# Gateway.net
KiCad netlist of a schematic drawn in EasyEDA Pro
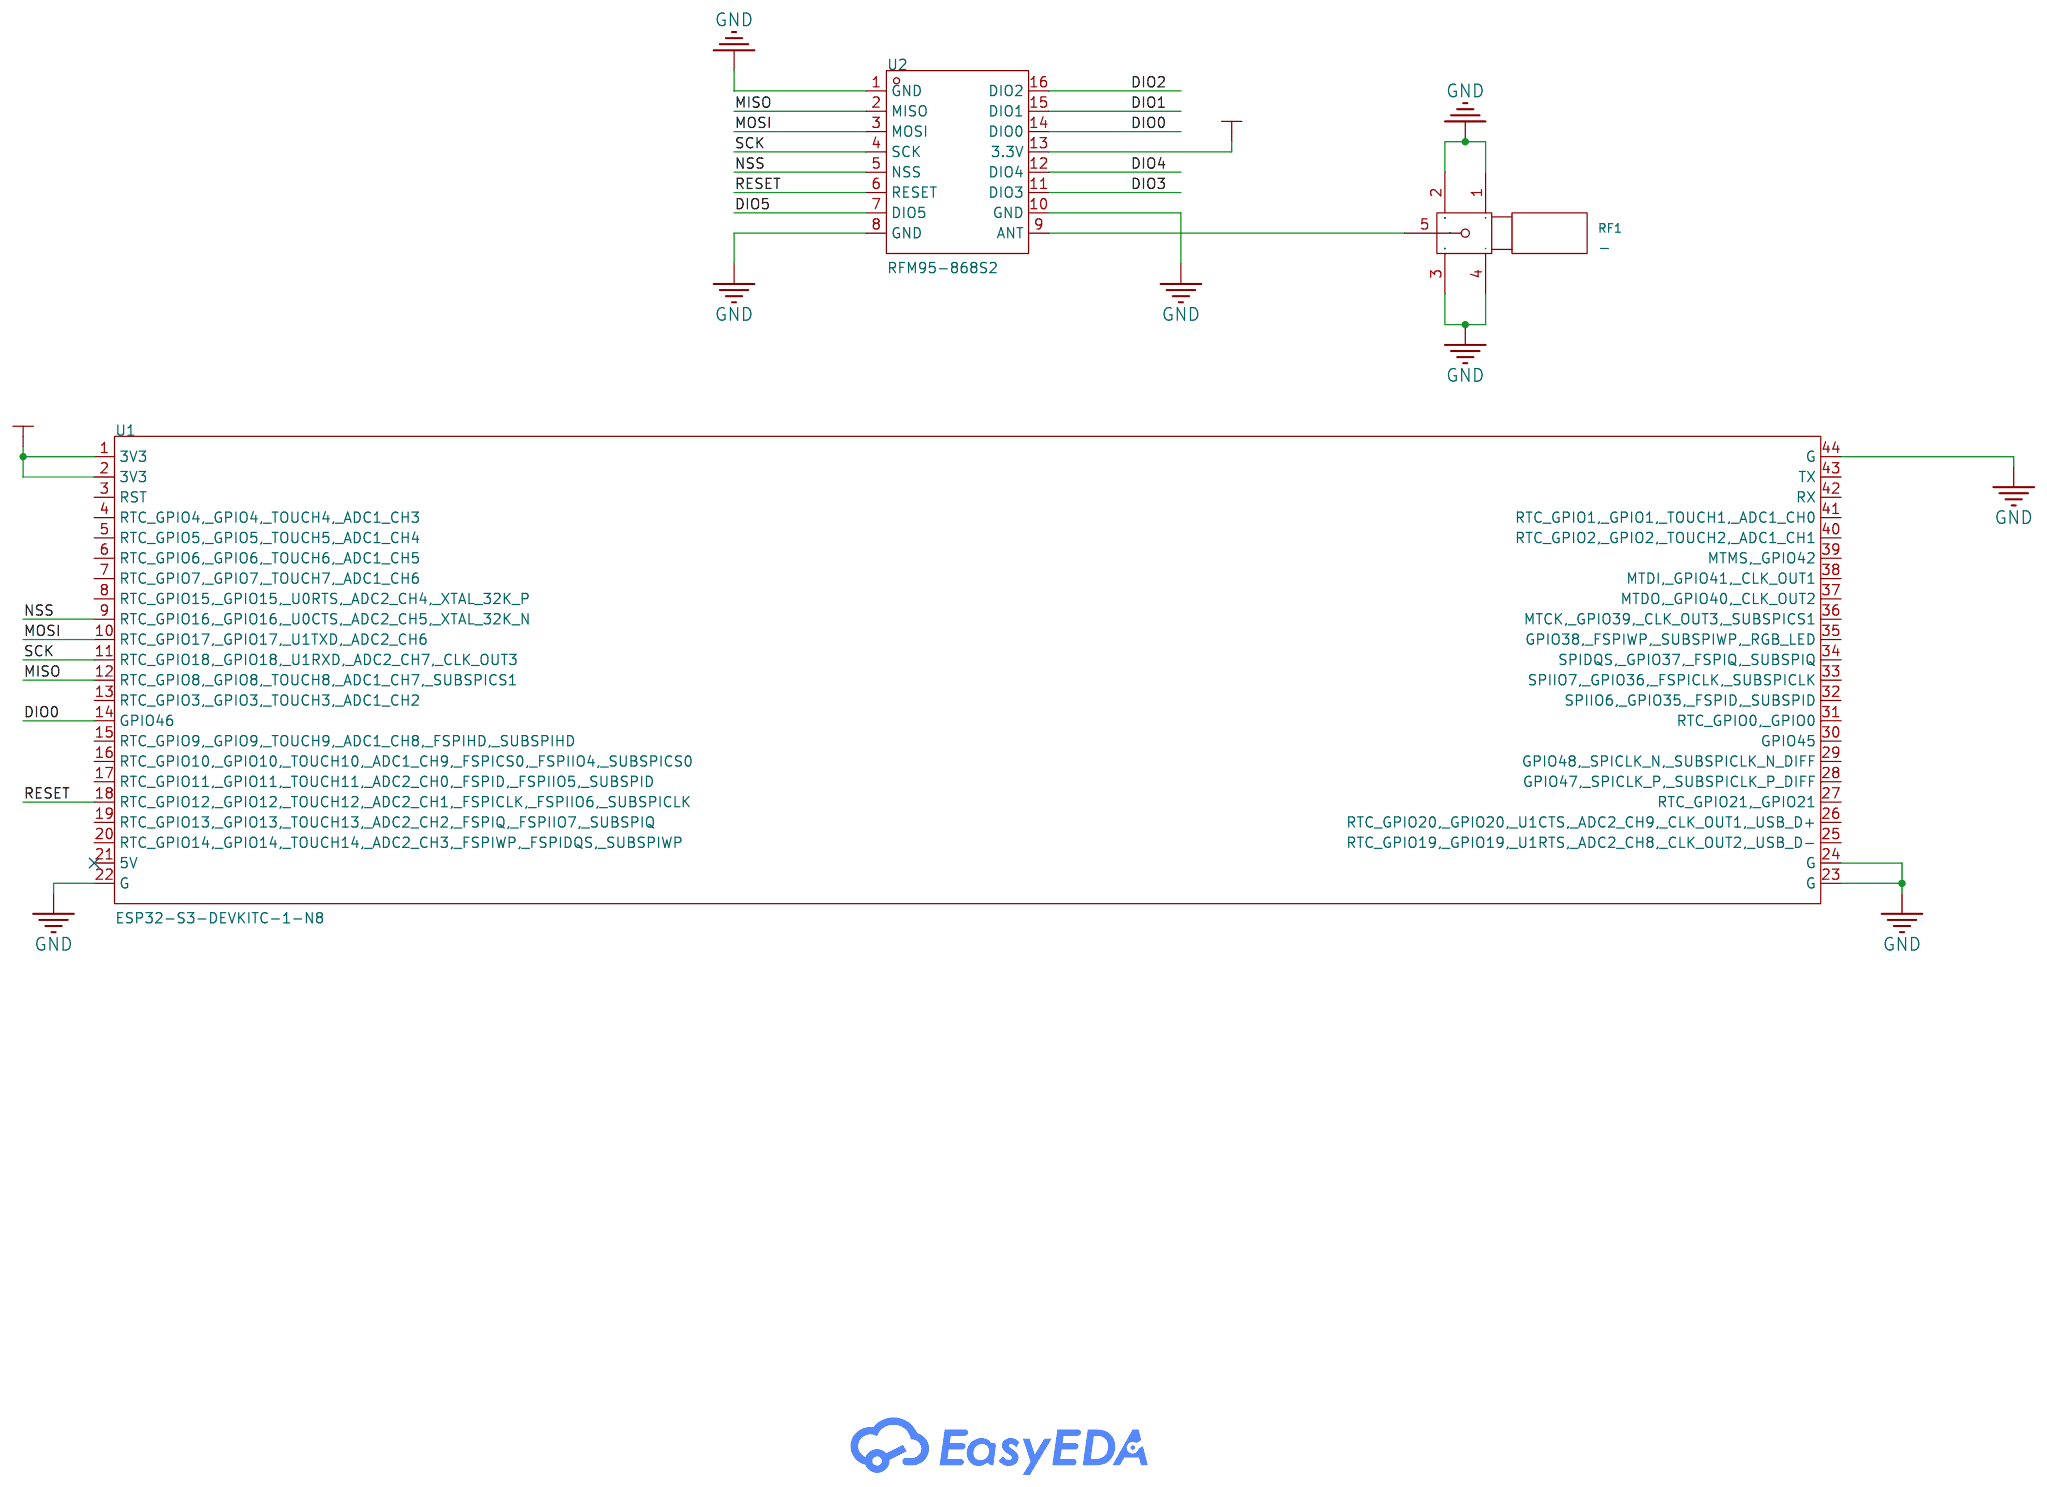
[diagram p0: schematic sheet]

(export (version "E")
  (design (tool "Eeschema 10.0.6"))
  (components
    (comp (ref "RF1")
      (value "-")
      (footprint "easyedapro:SMA-TH_BWSMA-KWE-Z001")
      (fields
        (field (name "Manufacturer Part") "BWSMA-KWE-Z001")
        (field (name "Manufacturer") "BAT WIRELESS(蝙蝠无线)")
      )
      (libsource (lib "easyedapro") (part "BWSMA-KWE-Z001"))
    )
    (comp (ref "U1")
      (value "ESP32-S3-DEVKITC-1-N8")
      (footprint "easyedapro:CONN-TH_ESP32-S3-DEVKITC-1U-N8")
      (fields (field (name "Manufacturer") "ESPRESSIF(乐鑫)"))
      (libsource (lib "easyedapro") (part "ESP32-S3-DEVKITC-1-N8"))
    )
    (comp (ref "U2")
      (value "RFM95-868S2")
      (footprint "easyedapro:WIRELM-SMD_RFM95-868S2")
      (fields (field (name "Manufacturer") "HOPERF(华普微电子)"))
      (libsource (lib "easyedapro") (part "RFM95-868S2"))
    )
  )
  (nets
    (net (code "1") (name "+3V3") (class "Default")
      (node (ref "U1") (pin "1") (pinfunction "3V3_1") (pintype "unspecified"))
      (node (ref "U1") (pin "2") (pinfunction "3V3_2") (pintype "unspecified"))
      (node (ref "U2") (pin "13") (pinfunction "3.3V_13") (pintype "unspecified"))
    )
    (net (code "2") (name "/DIO0") (class "Default")
      (node (ref "U1") (pin "14") (pinfunction "GPIO46_14") (pintype "unspecified"))
      (node (ref "U2") (pin "14") (pinfunction "DIO0_14") (pintype "unspecified"))
    )
    (net (code "3") (name "/DIO1") (class "Default")
      (node (ref "U2") (pin "15") (pinfunction "DIO1_15") (pintype "unspecified"))
    )
    (net (code "4") (name "/DIO2") (class "Default")
      (node (ref "U2") (pin "16") (pinfunction "DIO2_16") (pintype "unspecified"))
    )
    (net (code "5") (name "/DIO3") (class "Default")
      (node (ref "U2") (pin "11") (pinfunction "DIO3_11") (pintype "unspecified"))
    )
    (net (code "6") (name "/DIO4") (class "Default")
      (node (ref "U2") (pin "12") (pinfunction "DIO4_12") (pintype "unspecified"))
    )
    (net (code "7") (name "/DIO5") (class "Default")
      (node (ref "U2") (pin "7") (pinfunction "DIO5_7") (pintype "unspecified"))
    )
    (net (code "8") (name "/MISO") (class "Default")
      (node (ref "U1") (pin "12") (pinfunction "RTC_GPIO8,_GPIO8,_TOUCH8,_ADC1_CH7,_SUBSPICS1_12") (pintype "unspecified"))
      (node (ref "U2") (pin "2") (pinfunction "MISO_2") (pintype "unspecified"))
    )
    (net (code "9") (name "/MOSI") (class "Default")
      (node (ref "U1") (pin "10") (pinfunction "RTC_GPIO17,_GPIO17,_U1TXD,_ADC2_CH6_10") (pintype "unspecified"))
      (node (ref "U2") (pin "3") (pinfunction "MOSI_3") (pintype "unspecified"))
    )
    (net (code "10") (name "/NSS") (class "Default")
      (node (ref "U1") (pin "9") (pinfunction "RTC_GPIO16,_GPIO16,_U0CTS,_ADC2_CH5,_XTAL_32K_N_9") (pintype "unspecified"))
      (node (ref "U2") (pin "5") (pinfunction "NSS_5") (pintype "unspecified"))
    )
    (net (code "11") (name "/RESET") (class "Default")
      (node (ref "U1") (pin "18") (pinfunction "RTC_GPIO12,_GPIO12,_TOUCH12,_ADC2_CH1,_FSPICLK,_FSPIIO6,_SUBSPICLK_18") (pintype "unspecified"))
      (node (ref "U2") (pin "6") (pinfunction "RESET_6") (pintype "unspecified"))
    )
    (net (code "12") (name "/SCK") (class "Default")
      (node (ref "U1") (pin "11") (pinfunction "RTC_GPIO18,_GPIO18,_U1RXD,_ADC2_CH7,_CLK_OUT3_11") (pintype "unspecified"))
      (node (ref "U2") (pin "4") (pinfunction "SCK_4") (pintype "unspecified"))
    )
    (net (code "13") (name "GND") (class "Default")
      (node (ref "RF1") (pin "1") (pinfunction "1_1") (pintype "input"))
      (node (ref "RF1") (pin "2") (pinfunction "2_2") (pintype "input"))
      (node (ref "RF1") (pin "3") (pinfunction "3_3") (pintype "input"))
      (node (ref "RF1") (pin "4") (pinfunction "4_4") (pintype "input"))
      (node (ref "U1") (pin "22") (pinfunction "G_22") (pintype "unspecified"))
      (node (ref "U1") (pin "23") (pinfunction "G_23") (pintype "unspecified"))
      (node (ref "U1") (pin "24") (pinfunction "G_24") (pintype "unspecified"))
      (node (ref "U1") (pin "44") (pinfunction "G_44") (pintype "unspecified"))
      (node (ref "U2") (pin "1") (pinfunction "GND_1") (pintype "unspecified"))
      (node (ref "U2") (pin "10") (pinfunction "GND_10") (pintype "unspecified"))
      (node (ref "U2") (pin "8") (pinfunction "GND_8") (pintype "unspecified"))
    )
    (net (code "14") (name "Net-(U2-ANT)") (class "Default")
      (node (ref "RF1") (pin "5") (pinfunction "5_5") (pintype "input"))
      (node (ref "U2") (pin "9") (pinfunction "ANT_9") (pintype "unspecified"))
    )
    (net (code "15") (name "unconnected-(U1-5V-Pad21)") (class "Default")
      (node (ref "U1") (pin "21") (pinfunction "5V_21") (pintype "unspecified+no_connect"))
    )
    (net (code "16") (name "unconnected-(U1-GPIO38,_FSPIWP,_SUBSPIWP,_RGB_LED-Pad35)") (class "Default")
      (node (ref "U1") (pin "35") (pinfunction "GPIO38,_FSPIWP,_SUBSPIWP,_RGB_LED_35") (pintype "unspecified"))
    )
    (net (code "17") (name "unconnected-(U1-GPIO45-Pad30)") (class "Default")
      (node (ref "U1") (pin "30") (pinfunction "GPIO45_30") (pintype "unspecified"))
    )
    (net (code "18") (name "unconnected-(U1-GPIO47,_SPICLK_P,_SUBSPICLK_P_DIFF-Pad28)") (class "Default")
      (node (ref "U1") (pin "28") (pinfunction "GPIO47,_SPICLK_P,_SUBSPICLK_P_DIFF_28") (pintype "unspecified"))
    )
    (net (code "19") (name "unconnected-(U1-GPIO48,_SPICLK_N,_SUBSPICLK_N_DIFF-Pad29)") (class "Default")
      (node (ref "U1") (pin "29") (pinfunction "GPIO48,_SPICLK_N,_SUBSPICLK_N_DIFF_29") (pintype "unspecified"))
    )
    (net (code "20") (name "unconnected-(U1-MTCK,_GPIO39,_CLK_OUT3,_SUBSPICS1-Pad36)") (class "Default")
      (node (ref "U1") (pin "36") (pinfunction "MTCK,_GPIO39,_CLK_OUT3,_SUBSPICS1_36") (pintype "unspecified"))
    )
    (net (code "21") (name "unconnected-(U1-MTDI,_GPIO41,_CLK_OUT1-Pad38)") (class "Default")
      (node (ref "U1") (pin "38") (pinfunction "MTDI,_GPIO41,_CLK_OUT1_38") (pintype "unspecified"))
    )
    (net (code "22") (name "unconnected-(U1-MTDO,_GPIO40,_CLK_OUT2-Pad37)") (class "Default")
      (node (ref "U1") (pin "37") (pinfunction "MTDO,_GPIO40,_CLK_OUT2_37") (pintype "unspecified"))
    )
    (net (code "23") (name "unconnected-(U1-MTMS,_GPIO42-Pad39)") (class "Default")
      (node (ref "U1") (pin "39") (pinfunction "MTMS,_GPIO42_39") (pintype "unspecified"))
    )
    (net (code "24") (name "unconnected-(U1-RST-Pad3)") (class "Default")
      (node (ref "U1") (pin "3") (pinfunction "RST_3") (pintype "unspecified"))
    )
    (net (code "25") (name "unconnected-(U1-RTC_GPIO0,_GPIO0-Pad31)") (class "Default")
      (node (ref "U1") (pin "31") (pinfunction "RTC_GPIO0,_GPIO0_31") (pintype "unspecified"))
    )
    (net (code "26") (name "unconnected-(U1-RTC_GPIO1,_GPIO1,_TOUCH1,_ADC1_CH0-Pad41)") (class "Default")
      (node (ref "U1") (pin "41") (pinfunction "RTC_GPIO1,_GPIO1,_TOUCH1,_ADC1_CH0_41") (pintype "unspecified"))
    )
    (net (code "27") (name "unconnected-(U1-RTC_GPIO2,_GPIO2,_TOUCH2,_ADC1_CH1-Pad40)") (class "Default")
      (node (ref "U1") (pin "40") (pinfunction "RTC_GPIO2,_GPIO2,_TOUCH2,_ADC1_CH1_40") (pintype "unspecified"))
    )
    (net (code "28") (name "unconnected-(U1-RTC_GPIO3,_GPIO3,_TOUCH3,_ADC1_CH2-Pad13)") (class "Default")
      (node (ref "U1") (pin "13") (pinfunction "RTC_GPIO3,_GPIO3,_TOUCH3,_ADC1_CH2_13") (pintype "unspecified"))
    )
    (net (code "29") (name "unconnected-(U1-RTC_GPIO4,_GPIO4,_TOUCH4,_ADC1_CH3-Pad4)") (class "Default")
      (node (ref "U1") (pin "4") (pinfunction "RTC_GPIO4,_GPIO4,_TOUCH4,_ADC1_CH3_4") (pintype "unspecified"))
    )
    (net (code "30") (name "unconnected-(U1-RTC_GPIO5,_GPIO5,_TOUCH5,_ADC1_CH4-Pad5)") (class "Default")
      (node (ref "U1") (pin "5") (pinfunction "RTC_GPIO5,_GPIO5,_TOUCH5,_ADC1_CH4_5") (pintype "unspecified"))
    )
    (net (code "31") (name "unconnected-(U1-RTC_GPIO6,_GPIO6,_TOUCH6,_ADC1_CH5-Pad6)") (class "Default")
      (node (ref "U1") (pin "6") (pinfunction "RTC_GPIO6,_GPIO6,_TOUCH6,_ADC1_CH5_6") (pintype "unspecified"))
    )
    (net (code "32") (name "unconnected-(U1-RTC_GPIO7,_GPIO7,_TOUCH7,_ADC1_CH6-Pad7)") (class "Default")
      (node (ref "U1") (pin "7") (pinfunction "RTC_GPIO7,_GPIO7,_TOUCH7,_ADC1_CH6_7") (pintype "unspecified"))
    )
    (net (code "33") (name "unconnected-(U1-RTC_GPIO9,_GPIO9,_TOUCH9,_ADC1_CH8,_FSPIHD,_SUBSPIHD-Pad15)") (class "Default")
      (node (ref "U1") (pin "15") (pinfunction "RTC_GPIO9,_GPIO9,_TOUCH9,_ADC1_CH8,_FSPIHD,_SUBSPIHD_15") (pintype "unspecified"))
    )
    (net (code "34") (name "unconnected-(U1-RTC_GPIO10,_GPIO10,_TOUCH10,_ADC1_CH9,_FSPICS0,_FSPIIO4,_SUBSPICS0-Pad16)") (class "Default")
      (node (ref "U1") (pin "16") (pinfunction "RTC_GPIO10,_GPIO10,_TOUCH10,_ADC1_CH9,_FSPICS0,_FSPIIO4,_SUBSPICS0_16") (pintype "unspecified"))
    )
    (net (code "35") (name "unconnected-(U1-RTC_GPIO11,_GPIO11,_TOUCH11,_ADC2_CH0,_FSPID,_FSPIIO5,_SUBSPID-Pad17)") (class "Default")
      (node (ref "U1") (pin "17") (pinfunction "RTC_GPIO11,_GPIO11,_TOUCH11,_ADC2_CH0,_FSPID,_FSPIIO5,_SUBSPID_17") (pintype "unspecified"))
    )
    (net (code "36") (name "unconnected-(U1-RTC_GPIO13,_GPIO13,_TOUCH13,_ADC2_CH2,_FSPIQ,_FSPIIO7,_SUBSPIQ-Pad19)") (class "Default")
      (node (ref "U1") (pin "19") (pinfunction "RTC_GPIO13,_GPIO13,_TOUCH13,_ADC2_CH2,_FSPIQ,_FSPIIO7,_SUBSPIQ_19") (pintype "unspecified"))
    )
    (net (code "37") (name "unconnected-(U1-RTC_GPIO14,_GPIO14,_TOUCH14,_ADC2_CH3,_FSPIWP,_FSPIDQS,_SUBSPIWP-Pad20)") (class "Default")
      (node (ref "U1") (pin "20") (pinfunction "RTC_GPIO14,_GPIO14,_TOUCH14,_ADC2_CH3,_FSPIWP,_FSPIDQS,_SUBSPIWP_20") (pintype "unspecified"))
    )
    (net (code "38") (name "unconnected-(U1-RTC_GPIO15,_GPIO15,_U0RTS,_ADC2_CH4,_XTAL_32K_P-Pad8)") (class "Default")
      (node (ref "U1") (pin "8") (pinfunction "RTC_GPIO15,_GPIO15,_U0RTS,_ADC2_CH4,_XTAL_32K_P_8") (pintype "unspecified"))
    )
    (net (code "39") (name "unconnected-(U1-RTC_GPIO19,_GPIO19,_U1RTS,_ADC2_CH8,_CLK_OUT2,_USB_D--Pad25)") (class "Default")
      (node (ref "U1") (pin "25") (pinfunction "RTC_GPIO19,_GPIO19,_U1RTS,_ADC2_CH8,_CLK_OUT2,_USB_D-_25") (pintype "unspecified"))
    )
    (net (code "40") (name "unconnected-(U1-RTC_GPIO20,_GPIO20,_U1CTS,_ADC2_CH9,_CLK_OUT1,_USB_D+-Pad26)") (class "Default")
      (node (ref "U1") (pin "26") (pinfunction "RTC_GPIO20,_GPIO20,_U1CTS,_ADC2_CH9,_CLK_OUT1,_USB_D+_26") (pintype "unspecified"))
    )
    (net (code "41") (name "unconnected-(U1-RTC_GPIO21,_GPIO21-Pad27)") (class "Default")
      (node (ref "U1") (pin "27") (pinfunction "RTC_GPIO21,_GPIO21_27") (pintype "unspecified"))
    )
    (net (code "42") (name "unconnected-(U1-RX-Pad42)") (class "Default")
      (node (ref "U1") (pin "42") (pinfunction "RX_42") (pintype "unspecified"))
    )
    (net (code "43") (name "unconnected-(U1-SPIDQS,_GPIO37,_FSPIQ,_SUBSPIQ-Pad34)") (class "Default")
      (node (ref "U1") (pin "34") (pinfunction "SPIDQS,_GPIO37,_FSPIQ,_SUBSPIQ_34") (pintype "unspecified"))
    )
    (net (code "44") (name "unconnected-(U1-SPIIO6,_GPIO35,_FSPID,_SUBSPID-Pad32)") (class "Default")
      (node (ref "U1") (pin "32") (pinfunction "SPIIO6,_GPIO35,_FSPID,_SUBSPID_32") (pintype "unspecified"))
    )
    (net (code "45") (name "unconnected-(U1-SPIIO7,_GPIO36,_FSPICLK,_SUBSPICLK-Pad33)") (class "Default")
      (node (ref "U1") (pin "33") (pinfunction "SPIIO7,_GPIO36,_FSPICLK,_SUBSPICLK_33") (pintype "unspecified"))
    )
    (net (code "46") (name "unconnected-(U1-TX-Pad43)") (class "Default")
      (node (ref "U1") (pin "43") (pinfunction "TX_43") (pintype "unspecified"))
    )
  )
)
